# ComfortMaps.net
KiCad netlist of a schematic drawn in EAGLE
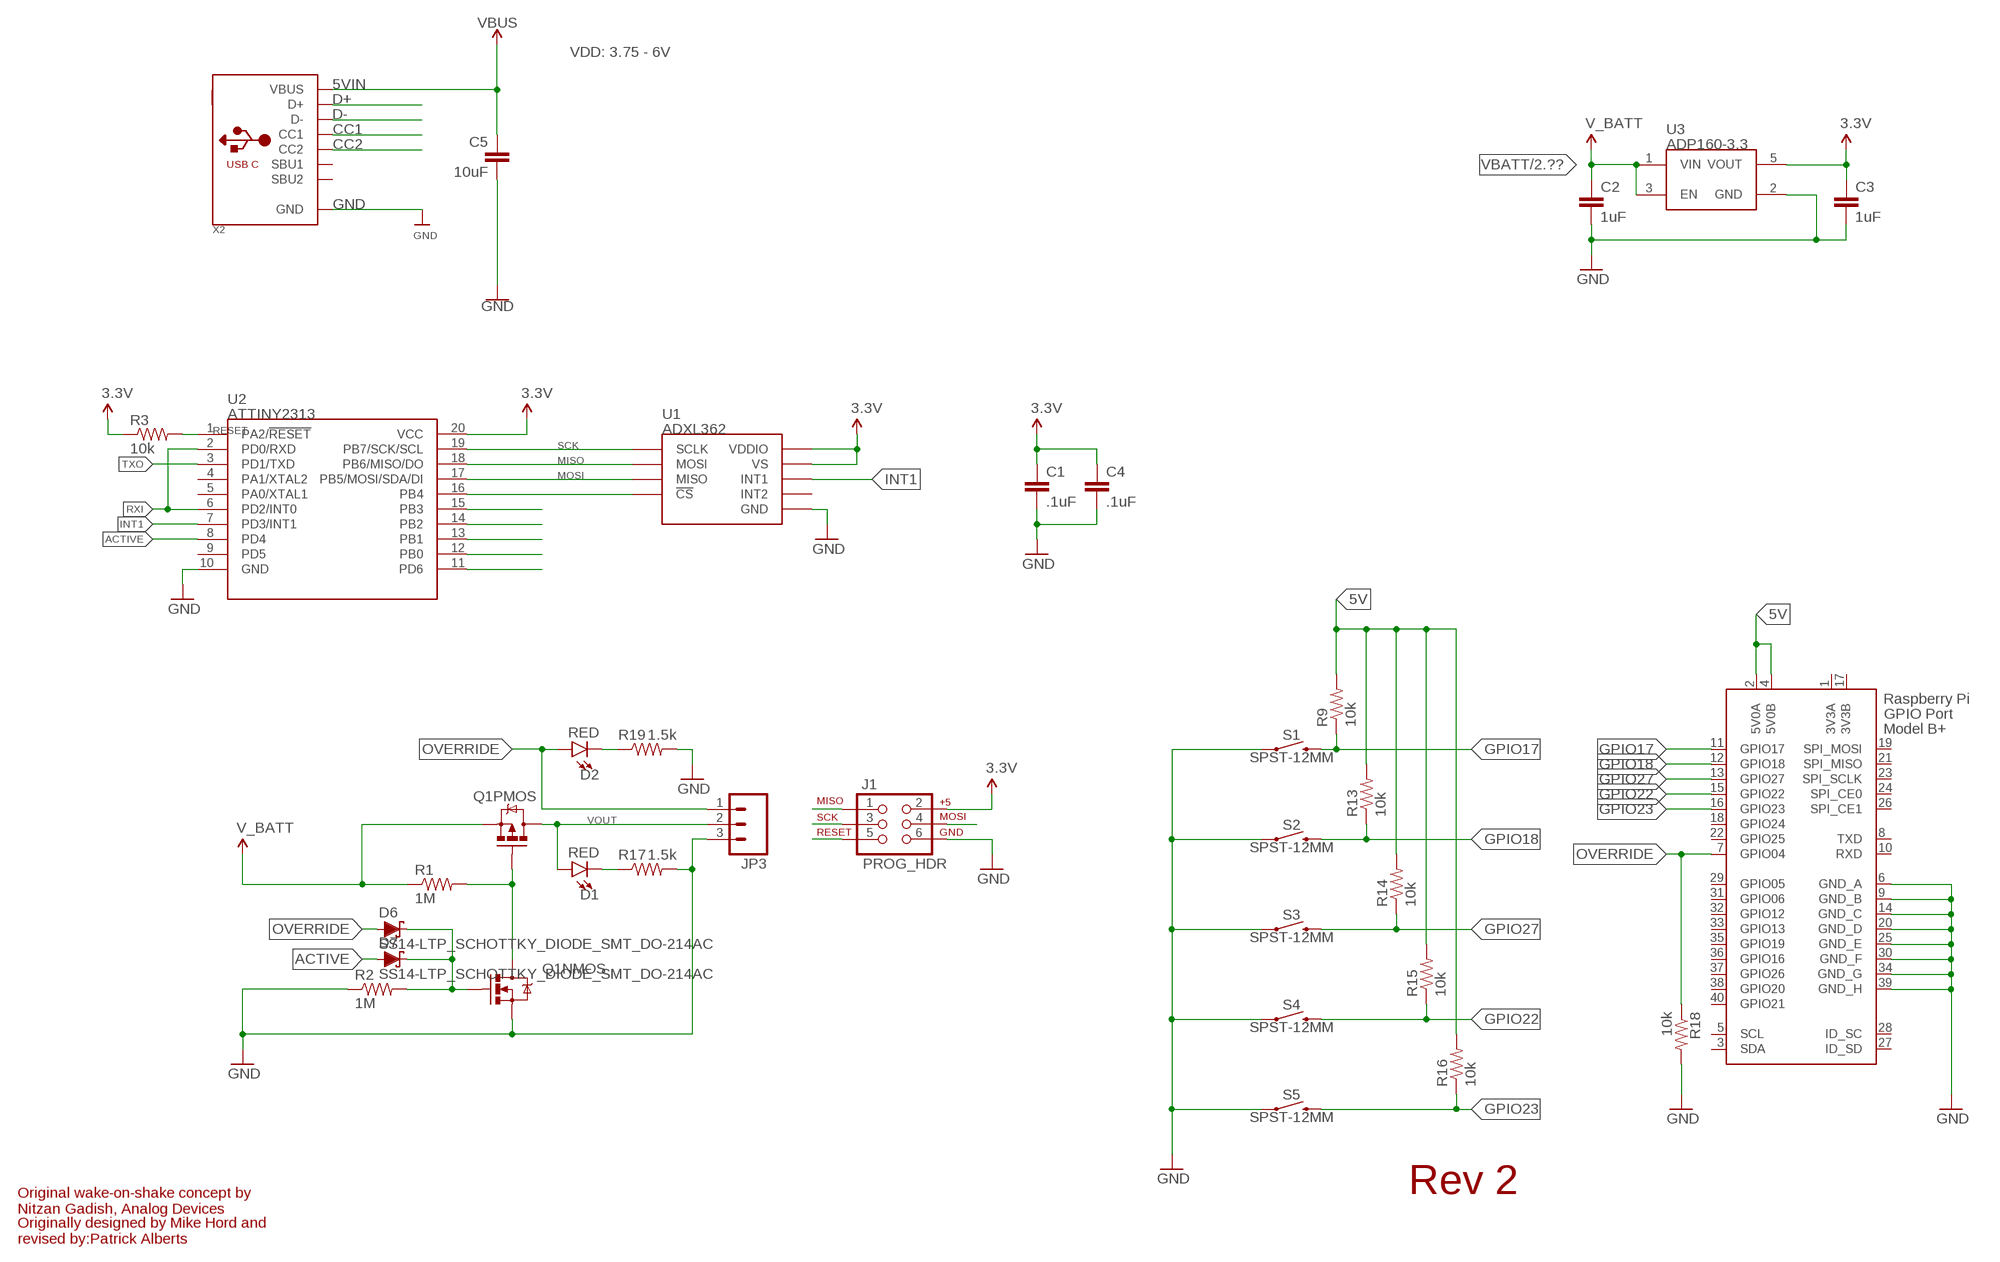
[diagram p0: schematic, sheet 1]
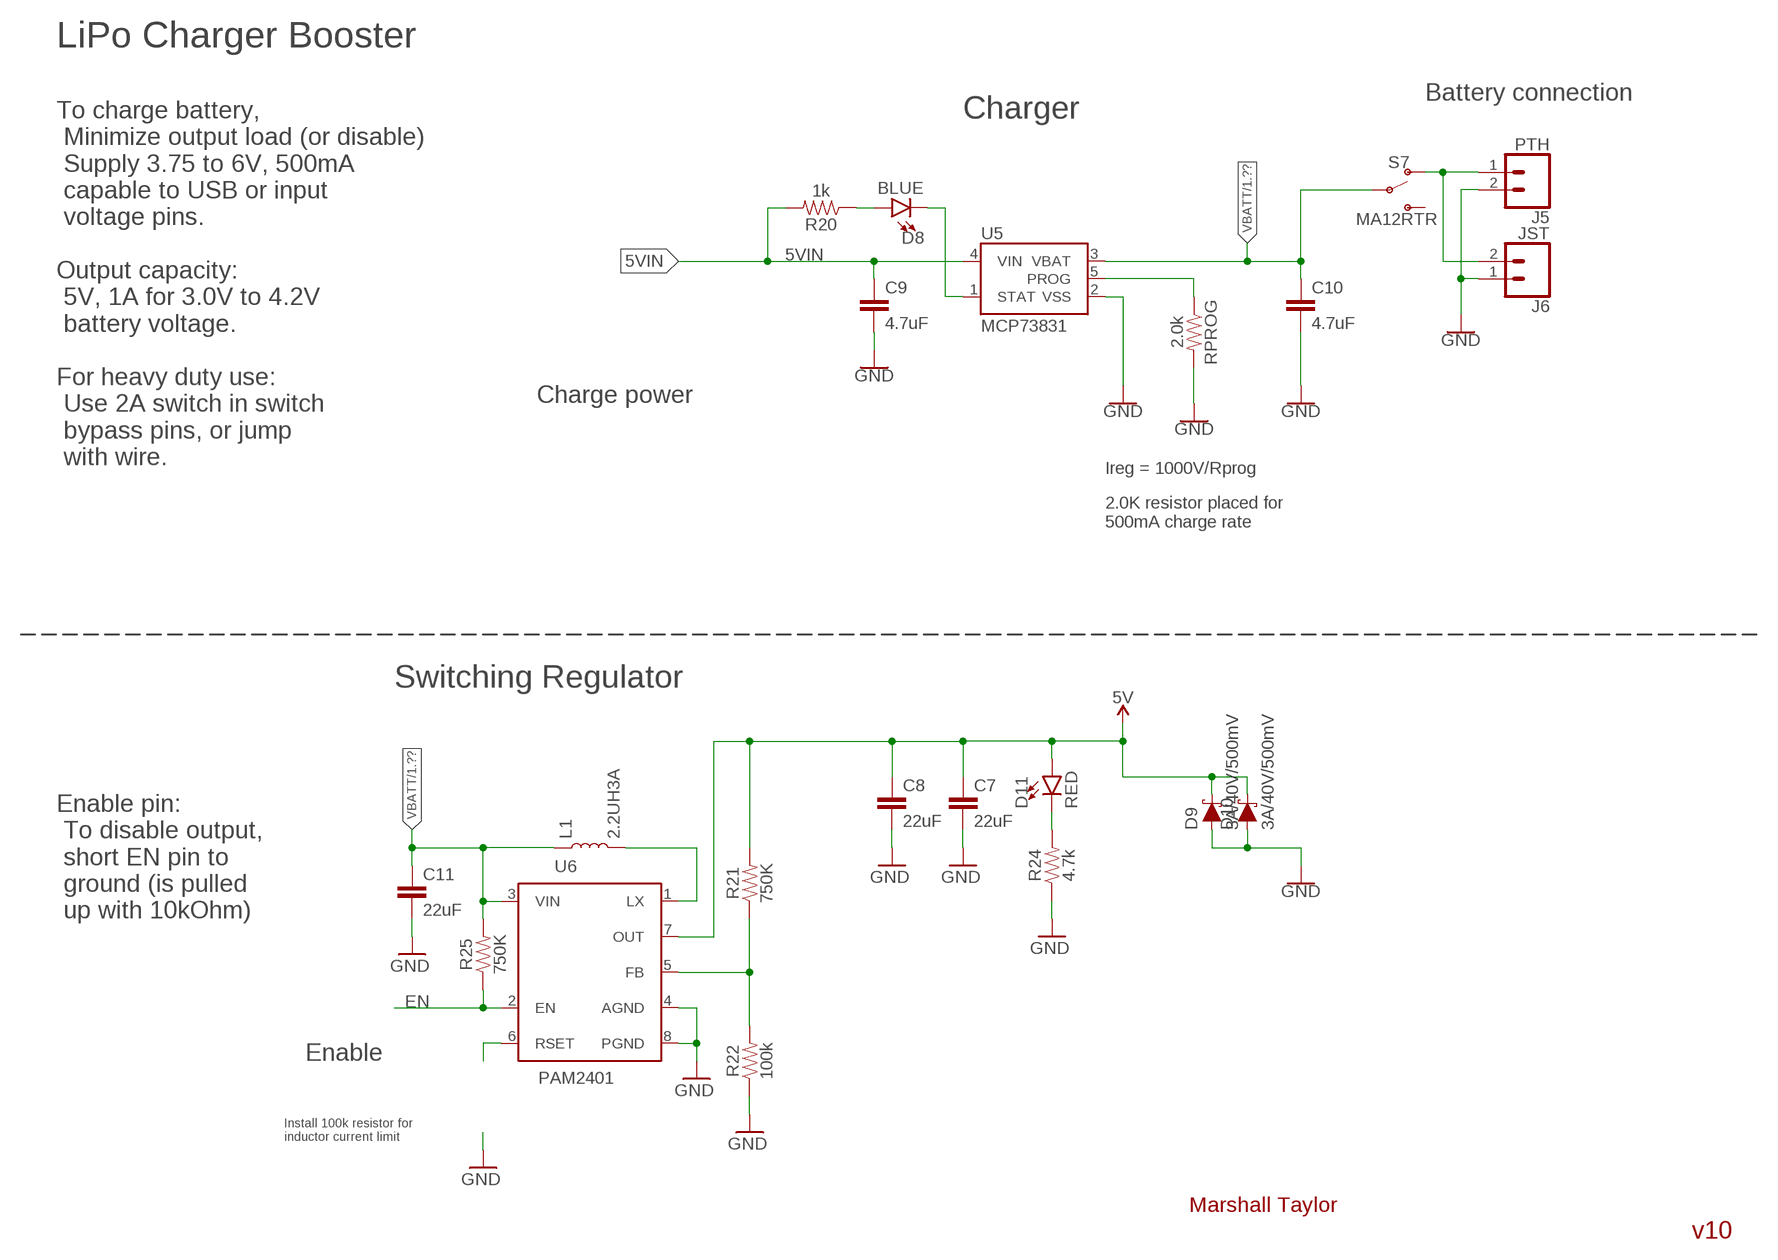
[diagram p1: schematic, sheet 2]

(export (version "E")
  (design (tool "Eeschema 10.0.6"))
  (components
    (comp (ref "C1")
      (value ".1uF")
      (footprint "eagle-import:0603-CAP")
      (fields (field (name "PROD_ID") "CAP-00810"))
      (libsource (lib "eagle-import") (part "0.1UF-25V(+80/-20%)(0603)"))
    )
    (comp (ref "C2")
      (value "1uF")
      (footprint "eagle-import:0603-CAP")
      (fields (field (name "PROD_ID") "CAP-00868"))
      (libsource (lib "eagle-import") (part "1.0UF-16V-10%(0603)"))
    )
    (comp (ref "C3")
      (value "1uF")
      (footprint "eagle-import:0603-CAP")
      (fields (field (name "PROD_ID") "CAP-00868"))
      (libsource (lib "eagle-import") (part "1.0UF-16V-10%(0603)"))
    )
    (comp (ref "C4")
      (value ".1uF")
      (footprint "eagle-import:0603-CAP")
      (fields (field (name "PROD_ID") "CAP-00810"))
      (libsource (lib "eagle-import") (part "0.1UF-25V(+80/-20%)(0603)"))
    )
    (comp (ref "C5")
      (value "10uF")
      (footprint "eagle-import:0603")
      (libsource (lib "eagle-import") (part "10UF-0603-6.3V-20%"))
    )
    (comp (ref "D1")
      (value "RED")
      (footprint "eagle-import:LED-0603")
      (libsource (lib "eagle-import") (part "LED-RED0603"))
    )
    (comp (ref "D2")
      (value "RED")
      (footprint "eagle-import:LED-0603")
      (libsource (lib "eagle-import") (part "LED-RED0603"))
    )
    (comp (ref "D6")
      (value "SS14-LTP_SCHOTTKY_DIODE_SMT_DO-214AC")
      (footprint "eagle-import:DO-214AC")
      (fields (field (name "MF") "Micro Commercial Co") (field (name "MPN") "SS14-LTP"))
      (libsource (lib "eagle-import") (part "SS14-LTP_SCHOTTKY_DIODE_SMT_DO-214AC"))
    )
    (comp (ref "D7")
      (value "SS14-LTP_SCHOTTKY_DIODE_SMT_DO-214AC")
      (footprint "eagle-import:DO-214AC")
      (fields (field (name "MF") "Micro Commercial Co") (field (name "MPN") "SS14-LTP"))
      (libsource (lib "eagle-import") (part "SS14-LTP_SCHOTTKY_DIODE_SMT_DO-214AC"))
    )
    (comp (ref "J1")
      (value "PROG_HDR")
      (footprint "eagle-import:2X3")
      (libsource (lib "eagle-import") (part "AVR_SPI_PRG_6PTH"))
    )
    (comp (ref "JP3")
      (value "M03PTH")
      (footprint "eagle-import:1X03")
      (libsource (lib "eagle-import") (part "M03PTH"))
    )
    (comp (ref "Q1")
      (value "IRF7509")
      (footprint "eagle-import:MSOP8")
      (fields (field (name "PROD_ID") "TRANS-07913"))
      (libsource (lib "eagle-import") (part "IRF7509"))
    )
    (comp (ref "R1")
      (value "1M")
      (footprint "eagle-import:0603-RES")
      (fields (field (name "PROD_ID") "RES-07868"))
      (libsource (lib "eagle-import") (part "1MOHM1/10W1%(0603)"))
    )
    (comp (ref "R2")
      (value "1M")
      (footprint "eagle-import:0603-RES")
      (fields (field (name "PROD_ID") "RES-07868"))
      (libsource (lib "eagle-import") (part "1MOHM1/10W1%(0603)"))
    )
    (comp (ref "R3")
      (value "10k")
      (footprint "eagle-import:0603-RES")
      (fields (field (name "PROD_ID") "RES-00824"))
      (libsource (lib "eagle-import") (part "10K-1%RES-00824"))
    )
    (comp (ref "R9")
      (value "10k")
      (footprint "eagle-import:0603-RES")
      (libsource (lib "eagle-import") (part "10K-1%RES-00824"))
    )
    (comp (ref "R13")
      (value "10k")
      (footprint "eagle-import:0603-RES")
      (libsource (lib "eagle-import") (part "10K-1%RES-00824"))
    )
    (comp (ref "R14")
      (value "10k")
      (footprint "eagle-import:0603-RES")
      (libsource (lib "eagle-import") (part "10K-1%RES-00824"))
    )
    (comp (ref "R15")
      (value "10k")
      (footprint "eagle-import:0603-RES")
      (libsource (lib "eagle-import") (part "10K-1%RES-00824"))
    )
    (comp (ref "R16")
      (value "10k")
      (footprint "eagle-import:0603-RES")
      (libsource (lib "eagle-import") (part "10K-1%RES-00824"))
    )
    (comp (ref "R17")
      (value "1.5k")
      (footprint "eagle-import:0603")
      (libsource (lib "eagle-import") (part "1.5KOHM-0603-1/10W-1%"))
    )
    (comp (ref "R18")
      (value "10k")
      (footprint "eagle-import:0603-RES")
      (libsource (lib "eagle-import") (part "10K-1%RES-00824"))
    )
    (comp (ref "R19")
      (value "1.5k")
      (footprint "eagle-import:0603")
      (libsource (lib "eagle-import") (part "1.5KOHM-0603-1/10W-1%"))
    )
    (comp (ref "S1")
      (value "SPST-12MM")
      (footprint "eagle-import:TACTILE_SWITCH_SMD_12MM")
      (libsource (lib "eagle-import") (part "MOMENTARY-SWITCH-SPST-SMD-12MM"))
    )
    (comp (ref "S2")
      (value "SPST-12MM")
      (footprint "eagle-import:TACTILE_SWITCH_SMD_12MM")
      (libsource (lib "eagle-import") (part "MOMENTARY-SWITCH-SPST-SMD-12MM"))
    )
    (comp (ref "S3")
      (value "SPST-12MM")
      (footprint "eagle-import:TACTILE_SWITCH_SMD_12MM")
      (libsource (lib "eagle-import") (part "MOMENTARY-SWITCH-SPST-SMD-12MM"))
    )
    (comp (ref "S4")
      (value "SPST-12MM")
      (footprint "eagle-import:TACTILE_SWITCH_SMD_12MM")
      (libsource (lib "eagle-import") (part "MOMENTARY-SWITCH-SPST-SMD-12MM"))
    )
    (comp (ref "S5")
      (value "SPST-12MM")
      (footprint "eagle-import:TACTILE_SWITCH_SMD_12MM")
      (libsource (lib "eagle-import") (part "MOMENTARY-SWITCH-SPST-SMD-12MM"))
    )
    (comp (ref "U1")
      (value "ADXL362")
      (footprint "eagle-import:ADXL362-1_1")
      (libsource (lib "eagle-import") (part "ADXL362ADXL362-1{colon}1"))
    )
    (comp (ref "U2")
      (value "ATTINY2313")
      (footprint "eagle-import:SOP20W")
      (libsource (lib "eagle-import") (part "ATTINY2313A"))
    )
    (comp (ref "U3")
      (value "ADP160-3.3")
      (footprint "eagle-import:SOT23-5")
      (libsource (lib "eagle-import") (part "ADP160"))
    )
    (comp (ref "X1")
      (value "RASPI_GPIO_B+#_PIN")
      (footprint "eagle-import:RASPI_GPIO_B+_PIN")
      (libsource (lib "eagle-import") (part "RASPI_GPIO_B+#_PIN"))
    )
    (comp (ref "X2")
      (value "USB_C")
      (footprint "eagle-import:USB_C_CUSB31-CFM2AX-01-X")
      (libsource (lib "eagle-import") (part "USB_C"))
    )
    (comp (ref "C7")
      (value "22uF")
      (footprint "eagle-import:0805")
      (libsource (lib "eagle-import") (part "22UF-0805-6.3V-20%"))
    )
    (comp (ref "C8")
      (value "22uF")
      (footprint "eagle-import:0805")
      (libsource (lib "eagle-import") (part "22UF-0805-6.3V-20%"))
    )
    (comp (ref "C9")
      (value "4.7uF")
      (footprint "eagle-import:0603")
      (libsource (lib "eagle-import") (part "4.7UF0603"))
    )
    (comp (ref "C10")
      (value "4.7uF")
      (footprint "eagle-import:0603")
      (libsource (lib "eagle-import") (part "4.7UF0603"))
    )
    (comp (ref "C11")
      (value "22uF")
      (footprint "eagle-import:0805")
      (libsource (lib "eagle-import") (part "22UF-0805-6.3V-20%"))
    )
    (comp (ref "D8")
      (value "BLUE")
      (footprint "eagle-import:LED-0603")
      (libsource (lib "eagle-import") (part "LED-BLUE0603"))
    )
    (comp (ref "D9")
      (value "3A/40V/500mV")
      (footprint "eagle-import:SMA-DIODE")
      (libsource (lib "eagle-import") (part "DIODE-SCHOTTKY-B340A"))
    )
    (comp (ref "D10")
      (value "3A/40V/500mV")
      (footprint "eagle-import:SMA-DIODE")
      (libsource (lib "eagle-import") (part "DIODE-SCHOTTKY-B340A"))
    )
    (comp (ref "D11")
      (value "RED")
      (footprint "eagle-import:LED-0603")
      (libsource (lib "eagle-import") (part "LED-RED0603"))
    )
    (comp (ref "J5")
      (value "PTH")
      (footprint "eagle-import:1X02")
      (libsource (lib "eagle-import") (part "CONN_02"))
    )
    (comp (ref "J6")
      (value "JST")
      (footprint "eagle-import:JST-2-SMD")
      (libsource (lib "eagle-import") (part "CONN_02-JST-2MM-SMT"))
    )
    (comp (ref "L1")
      (value "2.2UH3A")
      (footprint "eagle-import:INDUCTOR_4X4MM")
      (libsource (lib "eagle-import") (part "INDUCTOR-IFSC1515AHER2R2M01"))
    )
    (comp (ref "R20")
      (value "1k")
      (footprint "eagle-import:0603")
      (libsource (lib "eagle-import") (part "1KOHM-0603-1/10W-1%"))
    )
    (comp (ref "R21")
      (value "750K")
      (footprint "eagle-import:0603")
      (libsource (lib "eagle-import") (part "750KOHM-0603-1/10W-1%"))
    )
    (comp (ref "R22")
      (value "100k")
      (footprint "eagle-import:0603")
      (libsource (lib "eagle-import") (part "100KOHM-0603-1/10W-1%"))
    )
    (comp (ref "R24")
      (value "4.7k")
      (footprint "eagle-import:0603")
      (libsource (lib "eagle-import") (part "4.7KOHM-0603-1/10W-1%"))
    )
    (comp (ref "R25")
      (value "750K")
      (footprint "eagle-import:0603")
      (libsource (lib "eagle-import") (part "750KOHM-0603-1/10W-1%"))
    )
    (comp (ref "RPROG")
      (value "2.0k")
      (footprint "eagle-import:0603")
      (libsource (lib "eagle-import") (part "2.0KOHM-0603-1/10W-5%"))
    )
    (comp (ref "S7")
      (value "MA12RTR")
      (footprint "eagle-import:SWITCH_SPST_SMD_A")
      (libsource (lib "eagle-import") (part "SWITCH-SPDT-SMD-RIGHT-ANGLE"))
    )
    (comp (ref "U5")
      (value "MCP73831")
      (footprint "eagle-import:SOT23-5")
      (libsource (lib "eagle-import") (part "MCP73831"))
    )
    (comp (ref "U6")
      (value "PAM2401")
      (footprint "eagle-import:MSOP8")
      (libsource (lib "eagle-import") (part "PAM2401"))
    )
  )
  (nets
    (net (code "1") (name "3.3V") (class "Default")
      (node (ref "C1") (pin "1") (pinfunction "1_1") (pintype "passive"))
      (node (ref "C3") (pin "1") (pinfunction "1_1") (pintype "passive"))
      (node (ref "C4") (pin "1") (pinfunction "1_1") (pintype "passive"))
      (node (ref "J1") (pin "2") (pinfunction "2_2") (pintype "passive"))
      (node (ref "R3") (pin "1") (pinfunction "1_1") (pintype "passive"))
      (node (ref "U1") (pin "P$1") (pinfunction "VDDIO_P$1") (pintype "bidirectional"))
      (node (ref "U1") (pin "P$14") (pinfunction "VS_P$14") (pintype "bidirectional"))
      (node (ref "U2") (pin "20") (pinfunction "VCC_20") (pintype "bidirectional"))
      (node (ref "U3") (pin "5") (pinfunction "VOUT_5") (pintype "bidirectional"))
    )
    (net (code "2") (name "3V3A") (class "Default")
      (node (ref "X1") (pin "1") (pinfunction "3V3A_1") (pintype "power_in"))
    )
    (net (code "3") (name "3V3B") (class "Default")
      (node (ref "X1") (pin "17") (pinfunction "3V3B_17") (pintype "power_in"))
    )
    (net (code "4") (name "5V") (class "Default")
      (node (ref "C7") (pin "1") (pinfunction "1_1") (pintype "passive"))
      (node (ref "C8") (pin "1") (pinfunction "1_1") (pintype "passive"))
      (node (ref "D10") (pin "C") (pinfunction "C_C") (pintype "passive"))
      (node (ref "D11") (pin "A") (pinfunction "A_A") (pintype "passive"))
      (node (ref "D9") (pin "C") (pinfunction "C_C") (pintype "passive"))
      (node (ref "R13") (pin "2") (pinfunction "2_2") (pintype "passive"))
      (node (ref "R14") (pin "2") (pinfunction "2_2") (pintype "passive"))
      (node (ref "R15") (pin "2") (pinfunction "2_2") (pintype "passive"))
      (node (ref "R16") (pin "2") (pinfunction "2_2") (pintype "passive"))
      (node (ref "R21") (pin "2") (pinfunction "2_2") (pintype "passive"))
      (node (ref "R9") (pin "2") (pinfunction "2_2") (pintype "passive"))
      (node (ref "U6") (pin "7") (pinfunction "OUT_7") (pintype "bidirectional"))
      (node (ref "X1") (pin "2") (pinfunction "5V0A_2") (pintype "power_in"))
      (node (ref "X1") (pin "4") (pinfunction "5V0B_4") (pintype "power_in"))
    )
    (net (code "5") (name "5VIN") (class "Default")
      (node (ref "C5") (pin "1") (pinfunction "1_1") (pintype "passive"))
      (node (ref "C9") (pin "1") (pinfunction "1_1") (pintype "passive"))
      (node (ref "R20") (pin "2") (pinfunction "2_2") (pintype "passive"))
      (node (ref "U5") (pin "4") (pinfunction "VIN_4") (pintype "power_in"))
      (node (ref "X2") (pin "A4B9") (pinfunction "VBUS_A4B9") (pintype "power_in"))
      (node (ref "X2") (pin "B4A9") (pinfunction "VBUS_B4A9") (pintype "power_in"))
    )
    (net (code "6") (name "ACTIVE") (class "Default")
      (node (ref "D7") (pin "A") (pinfunction "A_A") (pintype "passive"))
      (node (ref "U2") (pin "8") (pinfunction "PD4_8") (pintype "bidirectional"))
    )
    (net (code "7") (name "CC1") (class "Default")
      (node (ref "X2") (pin "A5") (pinfunction "CC1_A5") (pintype "bidirectional"))
    )
    (net (code "8") (name "CC2") (class "Default")
      (node (ref "X2") (pin "B5") (pinfunction "CC2_B5") (pintype "bidirectional"))
    )
    (net (code "9") (name "D+") (class "Default")
      (node (ref "X2") (pin "A6") (pinfunction "D+_A6") (pintype "bidirectional"))
      (node (ref "X2") (pin "B6") (pinfunction "D+_B6") (pintype "bidirectional"))
    )
    (net (code "10") (name "D-") (class "Default")
      (node (ref "X2") (pin "A7") (pinfunction "D-_A7") (pintype "bidirectional"))
      (node (ref "X2") (pin "B7") (pinfunction "D-_B7") (pintype "bidirectional"))
    )
    (net (code "11") (name "EN") (class "Default")
      (node (ref "R25") (pin "1") (pinfunction "1_1") (pintype "passive"))
      (node (ref "U6") (pin "2") (pinfunction "EN_2") (pintype "bidirectional"))
    )
    (net (code "12") (name "GND") (class "Default")
      (node (ref "C1") (pin "2") (pinfunction "2_2") (pintype "passive"))
      (node (ref "C10") (pin "2") (pinfunction "2_2") (pintype "passive"))
      (node (ref "C11") (pin "2") (pinfunction "2_2") (pintype "passive"))
      (node (ref "C2") (pin "2") (pinfunction "2_2") (pintype "passive"))
      (node (ref "C3") (pin "2") (pinfunction "2_2") (pintype "passive"))
      (node (ref "C4") (pin "2") (pinfunction "2_2") (pintype "passive"))
      (node (ref "C5") (pin "2") (pinfunction "2_2") (pintype "passive"))
      (node (ref "C7") (pin "2") (pinfunction "2_2") (pintype "passive"))
      (node (ref "C8") (pin "2") (pinfunction "2_2") (pintype "passive"))
      (node (ref "C9") (pin "2") (pinfunction "2_2") (pintype "passive"))
      (node (ref "D10") (pin "A") (pinfunction "A_A") (pintype "passive"))
      (node (ref "D9") (pin "A") (pinfunction "A_A") (pintype "passive"))
      (node (ref "J1") (pin "6") (pinfunction "6_6") (pintype "passive"))
      (node (ref "J5") (pin "2") (pinfunction "2_2") (pintype "passive"))
      (node (ref "J6") (pin "1") (pinfunction "2_1") (pintype "passive"))
      (node (ref "JP3") (pin "3") (pinfunction "3_3") (pintype "passive"))
      (node (ref "Q1") (pin "1") (pinfunction "S_1") (pintype "passive"))
      (node (ref "R17") (pin "2") (pinfunction "2_2") (pintype "passive"))
      (node (ref "R18") (pin "2") (pinfunction "2_2") (pintype "passive"))
      (node (ref "R19") (pin "2") (pinfunction "2_2") (pintype "passive"))
      (node (ref "R2") (pin "1") (pinfunction "1_1") (pintype "passive"))
      (node (ref "R22") (pin "1") (pinfunction "1_1") (pintype "passive"))
      (node (ref "R24") (pin "1") (pinfunction "1_1") (pintype "passive"))
      (node (ref "RPROG") (pin "2") (pinfunction "2_2") (pintype "passive"))
      (node (ref "S1") (pin "1") (pinfunction "1_1") (pintype "passive"))
      (node (ref "S1") (pin "2") (pinfunction "1_2") (pintype "passive"))
      (node (ref "S2") (pin "1") (pinfunction "1_1") (pintype "passive"))
      (node (ref "S2") (pin "2") (pinfunction "1_2") (pintype "passive"))
      (node (ref "S3") (pin "1") (pinfunction "1_1") (pintype "passive"))
      (node (ref "S3") (pin "2") (pinfunction "1_2") (pintype "passive"))
      (node (ref "S4") (pin "1") (pinfunction "1_1") (pintype "passive"))
      (node (ref "S4") (pin "2") (pinfunction "1_2") (pintype "passive"))
      (node (ref "S5") (pin "1") (pinfunction "1_1") (pintype "passive"))
      (node (ref "S5") (pin "2") (pinfunction "1_2") (pintype "passive"))
      (node (ref "U1") (pin "P$12") (pinfunction "GND_P$12") (pintype "bidirectional"))
      (node (ref "U1") (pin "P$13") (pinfunction "GND_P$13") (pintype "bidirectional"))
      (node (ref "U1") (pin "P$16") (pinfunction "GND_P$16") (pintype "bidirectional"))
      (node (ref "U2") (pin "10") (pinfunction "GND_10") (pintype "bidirectional"))
      (node (ref "U3") (pin "2") (pinfunction "GND_2") (pintype "bidirectional"))
      (node (ref "U5") (pin "2") (pinfunction "VSS_2") (pintype "power_in"))
      (node (ref "U6") (pin "4") (pinfunction "AGND_4") (pintype "bidirectional"))
      (node (ref "U6") (pin "8") (pinfunction "PGND_8") (pintype "bidirectional"))
      (node (ref "X1") (pin "14") (pinfunction "GND_C_14") (pintype "power_in"))
      (node (ref "X1") (pin "20") (pinfunction "GND_D_20") (pintype "power_in"))
      (node (ref "X1") (pin "25") (pinfunction "GND_E_25") (pintype "power_in"))
      (node (ref "X1") (pin "30") (pinfunction "GND_F_30") (pintype "power_in"))
      (node (ref "X1") (pin "34") (pinfunction "GND_G_34") (pintype "power_in"))
      (node (ref "X1") (pin "39") (pinfunction "GND_H_39") (pintype "power_in"))
      (node (ref "X1") (pin "6") (pinfunction "GND_A_6") (pintype "power_in"))
      (node (ref "X1") (pin "9") (pinfunction "GND_B_9") (pintype "power_in"))
      (node (ref "X2") (pin "A1B12") (pinfunction "GND_A1B12") (pintype "power_in"))
      (node (ref "X2") (pin "B1A12") (pinfunction "GND_B1A12") (pintype "power_in"))
    )
    (net (code "13") (name "GPIO17") (class "Default")
      (node (ref "R9") (pin "1") (pinfunction "1_1") (pintype "passive"))
      (node (ref "S1") (pin "3") (pinfunction "2_3") (pintype "passive"))
      (node (ref "S1") (pin "4") (pinfunction "2_4") (pintype "passive"))
      (node (ref "X1") (pin "11") (pinfunction "GPIO17_11") (pintype "bidirectional"))
    )
    (net (code "14") (name "GPIO18") (class "Default")
      (node (ref "R13") (pin "1") (pinfunction "1_1") (pintype "passive"))
      (node (ref "S2") (pin "3") (pinfunction "2_3") (pintype "passive"))
      (node (ref "S2") (pin "4") (pinfunction "2_4") (pintype "passive"))
      (node (ref "X1") (pin "12") (pinfunction "GPIO18_12") (pintype "bidirectional"))
    )
    (net (code "15") (name "GPIO22") (class "Default")
      (node (ref "R15") (pin "1") (pinfunction "1_1") (pintype "passive"))
      (node (ref "S4") (pin "3") (pinfunction "2_3") (pintype "passive"))
      (node (ref "S4") (pin "4") (pinfunction "2_4") (pintype "passive"))
      (node (ref "X1") (pin "15") (pinfunction "GPIO22_15") (pintype "bidirectional"))
    )
    (net (code "16") (name "GPIO23") (class "Default")
      (node (ref "R16") (pin "1") (pinfunction "1_1") (pintype "passive"))
      (node (ref "S5") (pin "3") (pinfunction "2_3") (pintype "passive"))
      (node (ref "S5") (pin "4") (pinfunction "2_4") (pintype "passive"))
      (node (ref "X1") (pin "16") (pinfunction "GPIO23_16") (pintype "bidirectional"))
    )
    (net (code "17") (name "GPIO27") (class "Default")
      (node (ref "R14") (pin "1") (pinfunction "1_1") (pintype "passive"))
      (node (ref "S3") (pin "3") (pinfunction "2_3") (pintype "passive"))
      (node (ref "S3") (pin "4") (pinfunction "2_4") (pintype "passive"))
      (node (ref "X1") (pin "13") (pinfunction "GPIO27_13") (pintype "bidirectional"))
    )
    (net (code "18") (name "INT1") (class "Default")
      (node (ref "U1") (pin "P$11") (pinfunction "INT1_P$11") (pintype "bidirectional"))
      (node (ref "U2") (pin "7") (pinfunction "PD3/INT1_7") (pintype "bidirectional"))
    )
    (net (code "19") (name "MISO") (class "Default")
      (node (ref "J1") (pin "1") (pinfunction "1_1") (pintype "passive"))
      (node (ref "U1") (pin "P$6") (pinfunction "MOSI_P$6") (pintype "bidirectional"))
      (node (ref "U2") (pin "18") (pinfunction "PB6/MISO/DO_18") (pintype "bidirectional"))
    )
    (net (code "20") (name "MOSI") (class "Default")
      (node (ref "J1") (pin "4") (pinfunction "4_4") (pintype "passive"))
      (node (ref "U1") (pin "P$7") (pinfunction "MISO_P$7") (pintype "bidirectional"))
      (node (ref "U2") (pin "17") (pinfunction "PB5/MOSI/SDA/DI_17") (pintype "bidirectional"))
    )
    (net (code "21") (name "Net-(D1-PadC)") (class "Default")
      (node (ref "D1") (pin "C") (pinfunction "C_C") (pintype "passive"))
      (node (ref "R17") (pin "1") (pinfunction "1_1") (pintype "passive"))
    )
    (net (code "22") (name "Net-(D2-PadC)") (class "Default")
      (node (ref "D2") (pin "C") (pinfunction "C_C") (pintype "passive"))
      (node (ref "R19") (pin "1") (pinfunction "1_1") (pintype "passive"))
    )
    (net (code "23") (name "Net-(D8-PadA)") (class "Default")
      (node (ref "D8") (pin "A") (pinfunction "A_A") (pintype "passive"))
      (node (ref "R20") (pin "1") (pinfunction "1_1") (pintype "passive"))
    )
    (net (code "24") (name "Net-(D11-PadC)") (class "Default")
      (node (ref "D11") (pin "C") (pinfunction "C_C") (pintype "passive"))
      (node (ref "R24") (pin "2") (pinfunction "2_2") (pintype "passive"))
    )
    (net (code "25") (name "Net-(J6-1)") (class "Default")
      (node (ref "J5") (pin "1") (pinfunction "1_1") (pintype "passive"))
      (node (ref "J6") (pin "2") (pinfunction "1_2") (pintype "passive"))
      (node (ref "S7") (pin "1") (pinfunction "O_1") (pintype "passive"))
    )
    (net (code "26") (name "Net-(L1-2)") (class "Default")
      (node (ref "L1") (pin "P$2") (pinfunction "2_P$2") (pintype "passive"))
      (node (ref "U6") (pin "1") (pinfunction "LX_1") (pintype "bidirectional"))
    )
    (net (code "27") (name "Net-(Q1A-G)") (class "Default")
      (node (ref "D6") (pin "C") (pinfunction "C_C") (pintype "passive"))
      (node (ref "D7") (pin "C") (pinfunction "C_C") (pintype "passive"))
      (node (ref "Q1") (pin "2") (pinfunction "G_2") (pintype "passive"))
      (node (ref "R2") (pin "2") (pinfunction "2_2") (pintype "passive"))
    )
    (net (code "28") (name "Net-(Q1B-G)") (class "Default")
      (node (ref "Q1") (pin "4") (pinfunction "G_4") (pintype "passive"))
      (node (ref "Q1") (pin "7") (pinfunction "D_7") (pintype "passive"))
      (node (ref "Q1") (pin "8") (pinfunction "D_8") (pintype "passive"))
      (node (ref "R1") (pin "2") (pinfunction "2_2") (pintype "passive"))
    )
    (net (code "29") (name "Net-(U1-~{CS})") (class "Default")
      (node (ref "U1") (pin "P$8") (pinfunction "~{CS}_P$8") (pintype "bidirectional"))
      (node (ref "U2") (pin "16") (pinfunction "PB4_16") (pintype "bidirectional"))
    )
    (net (code "30") (name "Net-(U5-PROG)") (class "Default")
      (node (ref "RPROG") (pin "1") (pinfunction "1_1") (pintype "passive"))
      (node (ref "U5") (pin "5") (pinfunction "PROG_5") (pintype "input"))
    )
    (net (code "31") (name "Net-(U5-STAT)") (class "Default")
      (node (ref "D8") (pin "C") (pinfunction "C_C") (pintype "passive"))
      (node (ref "U5") (pin "1") (pinfunction "STAT_1") (pintype "output"))
    )
    (net (code "32") (name "Net-(U6-FB)") (class "Default")
      (node (ref "R21") (pin "1") (pinfunction "1_1") (pintype "passive"))
      (node (ref "R22") (pin "2") (pinfunction "2_2") (pintype "passive"))
      (node (ref "U6") (pin "5") (pinfunction "FB_5") (pintype "bidirectional"))
    )
    (net (code "33") (name "OVERRIDE") (class "Default")
      (node (ref "D2") (pin "A") (pinfunction "A_A") (pintype "passive"))
      (node (ref "D6") (pin "A") (pinfunction "A_A") (pintype "passive"))
      (node (ref "JP3") (pin "1") (pinfunction "1_1") (pintype "passive"))
      (node (ref "R18") (pin "1") (pinfunction "1_1") (pintype "passive"))
      (node (ref "X1") (pin "7") (pinfunction "GPIO04_7") (pintype "bidirectional"))
    )
    (net (code "34") (name "RESET") (class "Default")
      (node (ref "J1") (pin "5") (pinfunction "5_5") (pintype "passive"))
      (node (ref "R3") (pin "2") (pinfunction "2_2") (pintype "passive"))
      (node (ref "U2") (pin "1") (pinfunction "PA2/~{RESET}_1") (pintype "bidirectional"))
    )
    (net (code "35") (name "RXI") (class "Default")
      (node (ref "U2") (pin "2") (pinfunction "PD0/RXD_2") (pintype "bidirectional"))
      (node (ref "U2") (pin "6") (pinfunction "PD2/INT0_6") (pintype "bidirectional"))
    )
    (net (code "36") (name "SCK") (class "Default")
      (node (ref "J1") (pin "3") (pinfunction "3_3") (pintype "passive"))
      (node (ref "U1") (pin "P$4") (pinfunction "SCLK_P$4") (pintype "bidirectional"))
      (node (ref "U2") (pin "19") (pinfunction "PB7/SCK/SCL_19") (pintype "bidirectional"))
    )
    (net (code "37") (name "TXO") (class "Default")
      (node (ref "U2") (pin "3") (pinfunction "PD1/TXD_3") (pintype "bidirectional"))
    )
    (net (code "38") (name "VBATT") (class "Default")
      (node (ref "C10") (pin "1") (pinfunction "1_1") (pintype "passive"))
      (node (ref "C11") (pin "1") (pinfunction "1_1") (pintype "passive"))
      (node (ref "C2") (pin "1") (pinfunction "1_1") (pintype "passive"))
      (node (ref "L1") (pin "P$1") (pinfunction "1_P$1") (pintype "passive"))
      (node (ref "Q1") (pin "3") (pinfunction "S_3") (pintype "passive"))
      (node (ref "R1") (pin "1") (pinfunction "1_1") (pintype "passive"))
      (node (ref "R25") (pin "2") (pinfunction "2_2") (pintype "passive"))
      (node (ref "S7") (pin "2") (pinfunction "P_2") (pintype "passive"))
      (node (ref "U3") (pin "1") (pinfunction "VIN_1") (pintype "bidirectional"))
      (node (ref "U3") (pin "3") (pinfunction "EN_3") (pintype "bidirectional"))
      (node (ref "U5") (pin "3") (pinfunction "VBAT_3") (pintype "power_in"))
      (node (ref "U6") (pin "3") (pinfunction "VIN_3") (pintype "bidirectional"))
    )
    (net (code "39") (name "VOUT") (class "Default")
      (node (ref "D1") (pin "A") (pinfunction "A_A") (pintype "passive"))
      (node (ref "JP3") (pin "2") (pinfunction "2_2") (pintype "passive"))
      (node (ref "Q1") (pin "5") (pinfunction "D_5") (pintype "passive"))
      (node (ref "Q1") (pin "6") (pinfunction "D_6") (pintype "passive"))
    )
    (net (code "40") (name "unconnected-(S7-S-Pad3)") (class "Default")
      (node (ref "S7") (pin "3") (pinfunction "S_3") (pintype "passive"))
    )
    (net (code "41") (name "unconnected-(U1-INT2-PadP$9)") (class "Default")
      (node (ref "U1") (pin "P$9") (pinfunction "INT2_P$9") (pintype "bidirectional"))
    )
    (net (code "42") (name "unconnected-(U2-PA0{slash}XTAL1-Pad5)") (class "Default")
      (node (ref "U2") (pin "5") (pinfunction "PA0/XTAL1_5") (pintype "bidirectional"))
    )
    (net (code "43") (name "unconnected-(U2-PA1{slash}XTAL2-Pad4)") (class "Default")
      (node (ref "U2") (pin "4") (pinfunction "PA1/XTAL2_4") (pintype "bidirectional"))
    )
    (net (code "44") (name "unconnected-(U2-PB0-Pad12)") (class "Default")
      (node (ref "U2") (pin "12") (pinfunction "PB0_12") (pintype "bidirectional"))
    )
    (net (code "45") (name "unconnected-(U2-PB1-Pad13)") (class "Default")
      (node (ref "U2") (pin "13") (pinfunction "PB1_13") (pintype "bidirectional"))
    )
    (net (code "46") (name "unconnected-(U2-PB2-Pad14)") (class "Default")
      (node (ref "U2") (pin "14") (pinfunction "PB2_14") (pintype "bidirectional"))
    )
    (net (code "47") (name "unconnected-(U2-PB3-Pad15)") (class "Default")
      (node (ref "U2") (pin "15") (pinfunction "PB3_15") (pintype "bidirectional"))
    )
    (net (code "48") (name "unconnected-(U2-PD5-Pad9)") (class "Default")
      (node (ref "U2") (pin "9") (pinfunction "PD5_9") (pintype "bidirectional"))
    )
    (net (code "49") (name "unconnected-(U2-PD6-Pad11)") (class "Default")
      (node (ref "U2") (pin "11") (pinfunction "PD6_11") (pintype "bidirectional"))
    )
    (net (code "50") (name "unconnected-(U6-RSET-Pad6)") (class "Default")
      (node (ref "U6") (pin "6") (pinfunction "RSET_6") (pintype "bidirectional"))
    )
    (net (code "51") (name "unconnected-(X1-GPIO05-Pad29)") (class "Default")
      (node (ref "X1") (pin "29") (pinfunction "GPIO05_29") (pintype "no_connect"))
    )
    (net (code "52") (name "unconnected-(X1-GPIO06-Pad31)") (class "Default")
      (node (ref "X1") (pin "31") (pinfunction "GPIO06_31") (pintype "no_connect"))
    )
    (net (code "53") (name "unconnected-(X1-GPIO12-Pad32)") (class "Default")
      (node (ref "X1") (pin "32") (pinfunction "GPIO12_32") (pintype "no_connect"))
    )
    (net (code "54") (name "unconnected-(X1-GPIO13-Pad33)") (class "Default")
      (node (ref "X1") (pin "33") (pinfunction "GPIO13_33") (pintype "no_connect"))
    )
    (net (code "55") (name "unconnected-(X1-GPIO16-Pad36)") (class "Default")
      (node (ref "X1") (pin "36") (pinfunction "GPIO16_36") (pintype "no_connect"))
    )
    (net (code "56") (name "unconnected-(X1-GPIO19-Pad35)") (class "Default")
      (node (ref "X1") (pin "35") (pinfunction "GPIO19_35") (pintype "no_connect"))
    )
    (net (code "57") (name "unconnected-(X1-GPIO20-Pad38)") (class "Default")
      (node (ref "X1") (pin "38") (pinfunction "GPIO20_38") (pintype "no_connect"))
    )
    (net (code "58") (name "unconnected-(X1-GPIO21-Pad40)") (class "Default")
      (node (ref "X1") (pin "40") (pinfunction "GPIO21_40") (pintype "no_connect"))
    )
    (net (code "59") (name "unconnected-(X1-GPIO24-Pad18)") (class "Default")
      (node (ref "X1") (pin "18") (pinfunction "GPIO24_18") (pintype "bidirectional"))
    )
    (net (code "60") (name "unconnected-(X1-GPIO25-Pad22)") (class "Default")
      (node (ref "X1") (pin "22") (pinfunction "GPIO25_22") (pintype "bidirectional"))
    )
    (net (code "61") (name "unconnected-(X1-GPIO26-Pad37)") (class "Default")
      (node (ref "X1") (pin "37") (pinfunction "GPIO26_37") (pintype "no_connect"))
    )
    (net (code "62") (name "unconnected-(X1-ID_SC-Pad28)") (class "Default")
      (node (ref "X1") (pin "28") (pinfunction "ID_SC_28") (pintype "no_connect"))
    )
    (net (code "63") (name "unconnected-(X1-ID_SD-Pad27)") (class "Default")
      (node (ref "X1") (pin "27") (pinfunction "ID_SD_27") (pintype "no_connect"))
    )
    (net (code "64") (name "unconnected-(X1-RXD-Pad10)") (class "Default")
      (node (ref "X1") (pin "10") (pinfunction "RXD_10") (pintype "bidirectional"))
    )
    (net (code "65") (name "unconnected-(X1-SCL-Pad5)") (class "Default")
      (node (ref "X1") (pin "5") (pinfunction "SCL_5") (pintype "bidirectional"))
    )
    (net (code "66") (name "unconnected-(X1-SDA-Pad3)") (class "Default")
      (node (ref "X1") (pin "3") (pinfunction "SDA_3") (pintype "bidirectional"))
    )
    (net (code "67") (name "unconnected-(X1-SPI_CE0-Pad24)") (class "Default")
      (node (ref "X1") (pin "24") (pinfunction "SPI_CE0_24") (pintype "bidirectional"))
    )
    (net (code "68") (name "unconnected-(X1-SPI_CE1-Pad26)") (class "Default")
      (node (ref "X1") (pin "26") (pinfunction "SPI_CE1_26") (pintype "bidirectional"))
    )
    (net (code "69") (name "unconnected-(X1-SPI_MISO-Pad21)") (class "Default")
      (node (ref "X1") (pin "21") (pinfunction "SPI_MISO_21") (pintype "bidirectional"))
    )
    (net (code "70") (name "unconnected-(X1-SPI_MOSI-Pad19)") (class "Default")
      (node (ref "X1") (pin "19") (pinfunction "SPI_MOSI_19") (pintype "bidirectional"))
    )
    (net (code "71") (name "unconnected-(X1-SPI_SCLK-Pad23)") (class "Default")
      (node (ref "X1") (pin "23") (pinfunction "SPI_SCLK_23") (pintype "bidirectional"))
    )
    (net (code "72") (name "unconnected-(X1-TXD-Pad8)") (class "Default")
      (node (ref "X1") (pin "8") (pinfunction "TXD_8") (pintype "bidirectional"))
    )
    (net (code "73") (name "unconnected-(X2-SBU1-PadA8)") (class "Default")
      (node (ref "X2") (pin "A8") (pinfunction "SBU1_A8") (pintype "bidirectional"))
    )
    (net (code "74") (name "unconnected-(X2-SBU2-PadB8)") (class "Default")
      (node (ref "X2") (pin "B8") (pinfunction "SBU2_B8") (pintype "bidirectional"))
    )
  )
)
